# MPPC_POS_FINALFINAL.net
KiCad netlist of a schematic drawn in EAGLE
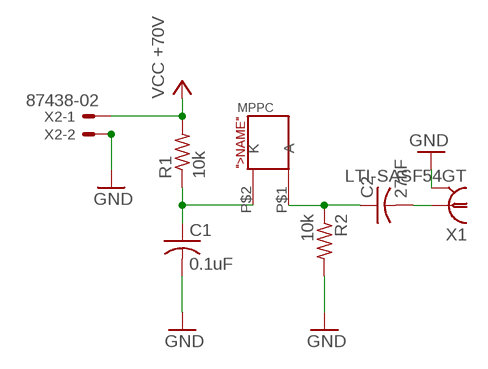
[diagram p0: schematic, sheet 1]

(export (version "E")
  (design (tool "Eeschema 10.0.6"))
  (components
    (comp (ref "C1")
      (value "0.1uF")
      (footprint "eagle-import:C1206")
      (libsource (lib "eagle-import") (part "C-USC1206"))
    )
    (comp (ref "C2")
      (value "27nF")
      (footprint "eagle-import:C1206")
      (libsource (lib "eagle-import") (part "C-USC1206"))
    )
    (comp (ref "R1")
      (value "10k")
      (footprint "eagle-import:R1206")
      (libsource (lib "eagle-import") (part "R-US_R1206"))
    )
    (comp (ref "R2")
      (value "10k")
      (footprint "eagle-import:R1206")
      (libsource (lib "eagle-import") (part "R-US_R1206"))
    )
    (comp (ref "U$1")
      (value "MPPC-S12572-025C")
      (footprint "eagle-import:MPPC_V2")
      (libsource (lib "eagle-import") (part "MPPC-S12572-025C"))
    )
    (comp (ref "X1")
      (value "LTI-SASF54GT")
      (footprint "eagle-import:LTI-SASF54GT")
      (libsource (lib "eagle-import") (part "LTI-SASF54GT"))
    )
    (comp (ref "X2")
      (value "87438-02")
      (footprint "eagle-import:87438-02")
      (libsource (lib "eagle-import") (part "87438-02"))
    )
  )
  (nets
    (net (code "1") (name "GND") (class "Default")
      (node (ref "C1") (pin "2") (pinfunction "2_2") (pintype "passive"))
      (node (ref "R2") (pin "2") (pinfunction "2_2") (pintype "passive"))
      (node (ref "X1") (pin "2") (pinfunction "2_2") (pintype "passive"))
      (node (ref "X1") (pin "3") (pinfunction "2_3") (pintype "passive"))
      (node (ref "X1") (pin "4") (pinfunction "2_4") (pintype "passive"))
      (node (ref "X1") (pin "5") (pinfunction "2_5") (pintype "passive"))
      (node (ref "X2") (pin "2") (pinfunction "S_2") (pintype "passive"))
    )
    (net (code "2") (name "Net-(C2-Pad2)") (class "Default")
      (node (ref "C2") (pin "2") (pinfunction "2_2") (pintype "passive"))
      (node (ref "X1") (pin "1") (pinfunction "1_1") (pintype "passive"))
    )
    (net (code "3") (name "Net-(U$1-A)") (class "Default")
      (node (ref "C2") (pin "1") (pinfunction "1_1") (pintype "passive"))
      (node (ref "R2") (pin "1") (pinfunction "1_1") (pintype "passive"))
      (node (ref "U$1") (pin "P$1") (pinfunction "A_P$1") (pintype "bidirectional"))
    )
    (net (code "4") (name "Net-(U$1-K)") (class "Default")
      (node (ref "C1") (pin "1") (pinfunction "1_1") (pintype "passive"))
      (node (ref "R1") (pin "1") (pinfunction "1_1") (pintype "passive"))
      (node (ref "U$1") (pin "P$2") (pinfunction "K_P$2") (pintype "bidirectional"))
    )
    (net (code "5") (name "VCC +70V") (class "Default")
      (node (ref "R1") (pin "2") (pinfunction "2_2") (pintype "passive"))
      (node (ref "X2") (pin "1") (pinfunction "S_1") (pintype "passive"))
    )
  )
)
